# Esp_Companion_V1.net
KiCad netlist of a schematic drawn in EAGLE
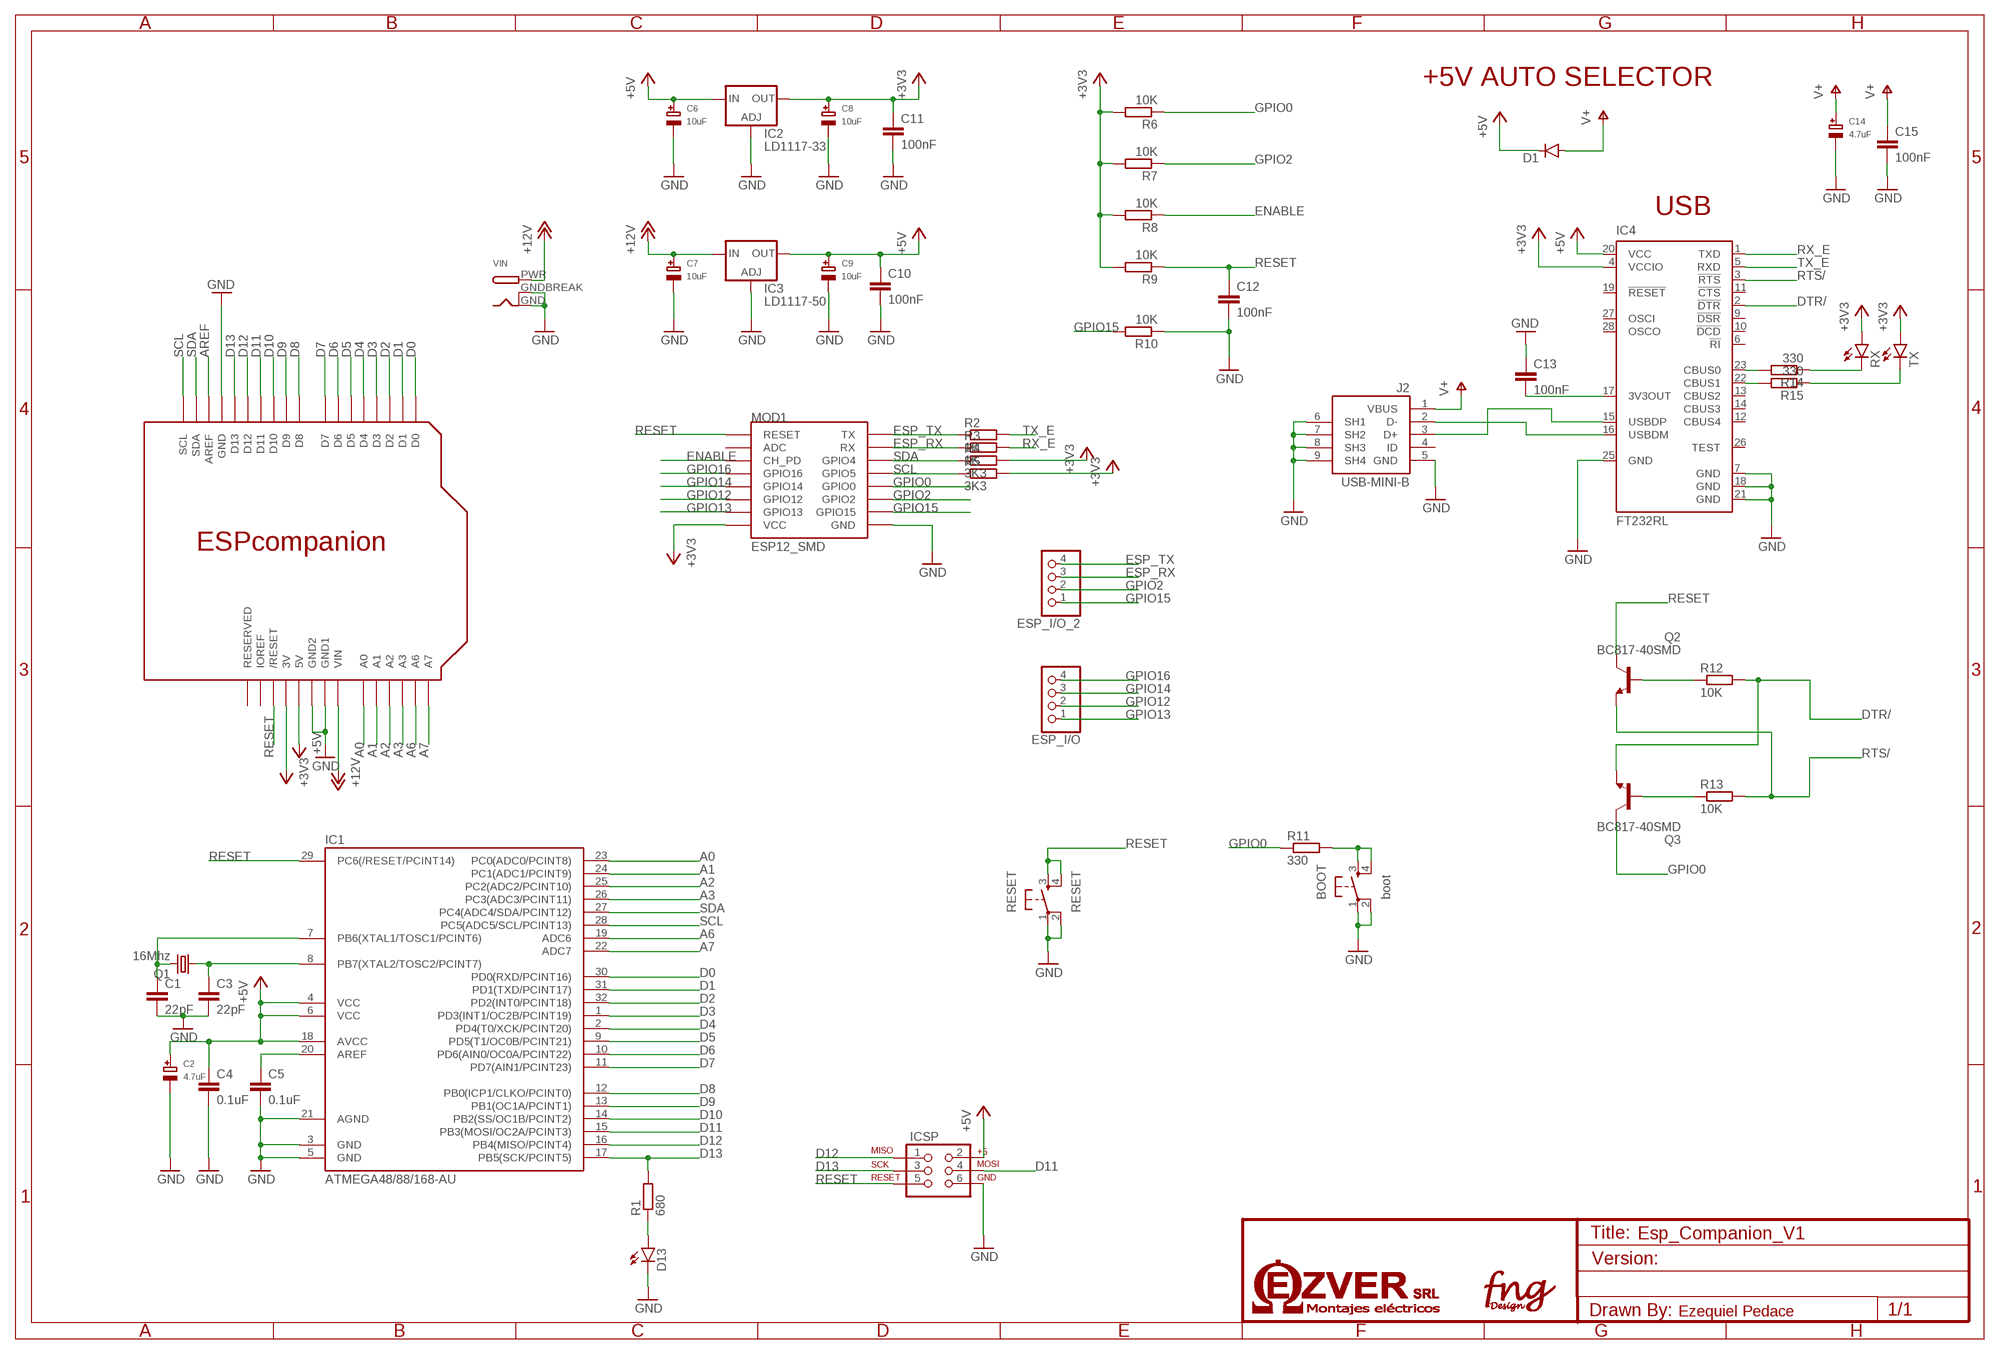
[diagram p0: schematic, sheet 1]

(export (version "E")
  (design (tool "Eeschema 10.0.6"))
  (components
    (comp (ref "BOOT")
      (value "boot")
      (footprint "eagle-import:TACTILE-PTH")
      (libsource (lib "eagle-import") (part "TAC_SWITCHPTH"))
    )
    (comp (ref "C1")
      (value "22pF")
      (footprint "eagle-import:C0603")
      (libsource (lib "eagle-import") (part "C-EUC0603"))
    )
    (comp (ref "C2")
      (value "4.7uF")
      (footprint "eagle-import:EIA3216-18_A-R")
      (libsource (lib "eagle-import") (part "CAP_TANTALUMA/3216_REFLOW"))
    )
    (comp (ref "C3")
      (value "22pF")
      (footprint "eagle-import:C0603")
      (libsource (lib "eagle-import") (part "C-EUC0603"))
    )
    (comp (ref "C4")
      (value "0.1uF")
      (footprint "eagle-import:C0603")
      (libsource (lib "eagle-import") (part "C-EUC0603"))
    )
    (comp (ref "C5")
      (value "0.1uF")
      (footprint "eagle-import:C0603")
      (libsource (lib "eagle-import") (part "C-EUC0603"))
    )
    (comp (ref "C6")
      (value "10uF")
      (footprint "eagle-import:EIA3216-18_A-R")
      (libsource (lib "eagle-import") (part "CAP_TANTALUMA/3216_REFLOW"))
    )
    (comp (ref "C7")
      (value "10uF")
      (footprint "eagle-import:EIA3216-18_A-R")
      (libsource (lib "eagle-import") (part "CAP_TANTALUMA/3216_REFLOW"))
    )
    (comp (ref "C8")
      (value "10uF")
      (footprint "eagle-import:EIA3216-18_A-R")
      (libsource (lib "eagle-import") (part "CAP_TANTALUMA/3216_REFLOW"))
    )
    (comp (ref "C9")
      (value "10uF")
      (footprint "eagle-import:EIA3216-18_A-R")
      (libsource (lib "eagle-import") (part "CAP_TANTALUMA/3216_REFLOW"))
    )
    (comp (ref "C10")
      (value "100nF")
      (footprint "eagle-import:C0603")
      (libsource (lib "eagle-import") (part "C-EUC0603"))
    )
    (comp (ref "C11")
      (value "100nF")
      (footprint "eagle-import:C0603")
      (libsource (lib "eagle-import") (part "C-EUC0603"))
    )
    (comp (ref "C12")
      (value "100nF")
      (footprint "eagle-import:C0603")
      (libsource (lib "eagle-import") (part "C-EUC0603"))
    )
    (comp (ref "C13")
      (value "100nF")
      (footprint "eagle-import:C0603")
      (libsource (lib "eagle-import") (part "C-EUC0603"))
    )
    (comp (ref "C14")
      (value "4.7uF")
      (footprint "eagle-import:EIA3216-18_A-R")
      (libsource (lib "eagle-import") (part "CAP_TANTALUMA/3216_REFLOW"))
    )
    (comp (ref "C15")
      (value "100nF")
      (footprint "eagle-import:C0603")
      (libsource (lib "eagle-import") (part "C-EUC0603"))
    )
    (comp (ref "D1")
      (value "DIODESMA-ALT")
      (footprint "eagle-import:SMA-DIODE_ALT")
      (libsource (lib "eagle-import") (part "DIODESMA-ALT"))
    )
    (comp (ref "D13")
      (value "LED-FKIT-1206")
      (footprint "eagle-import:FKIT-LED-1206")
      (libsource (lib "eagle-import") (part "LED-FKIT-1206"))
    )
    (comp (ref "ESP_I/O")
      (value "PINHD-1X4")
      (footprint "eagle-import:1X04")
      (libsource (lib "eagle-import") (part "PINHD-1X4"))
    )
    (comp (ref "ESP_I/O_2")
      (value "PINHD-1X4")
      (footprint "eagle-import:1X04")
      (libsource (lib "eagle-import") (part "PINHD-1X4"))
    )
    (comp (ref "IC1")
      (value "ATMEGA48/88/168-AU")
      (footprint "eagle-import:TQFP32-08")
      (libsource (lib "eagle-import") (part "ATMEGA48/88/168-AU"))
    )
    (comp (ref "IC2")
      (value "LD1117-33")
      (footprint "eagle-import:DPACK")
      (libsource (lib "eagle-import") (part "LD117A?DT33TR"))
    )
    (comp (ref "IC3")
      (value "LD1117-50")
      (footprint "eagle-import:DPACK")
      (libsource (lib "eagle-import") (part "LD117A?DT33TR"))
    )
    (comp (ref "IC4")
      (value "FT232RL")
      (footprint "eagle-import:SSOP28")
      (libsource (lib "eagle-import") (part "FT232RL"))
    )
    (comp (ref "ICSP")
      (value "AVR_SPI_PRG_62X3_LOCK")
      (footprint "eagle-import:2X3_LOCK")
      (libsource (lib "eagle-import") (part "AVR_SPI_PRG_62X3_LOCK"))
    )
    (comp (ref "J2")
      (value "USB-MINI-B")
      (footprint "eagle-import:USB-MINI-B")
      (libsource (lib "eagle-import") (part "USB-MINI-B"))
    )
    (comp (ref "LAY1")
      (value "ESPCOMPANIONHOLES")
      (footprint "eagle-import:ESPCOMPANION_HOLES")
      (libsource (lib "eagle-import") (part "ESPCOMPANIONHOLES"))
    )
    (comp (ref "MOD1")
      (value "ESP12_SMD")
      (footprint "eagle-import:ESP12_SMD")
      (libsource (lib "eagle-import") (part "ESP12_SMD"))
    )
    (comp (ref "Q1")
      (value "16Mhz")
      (footprint "eagle-import:HC49U70")
      (libsource (lib "eagle-import") (part "CRYSTALHC49U70"))
    )
    (comp (ref "Q2")
      (value "BC817-40SMD")
      (footprint "eagle-import:SOT23-BEC")
      (libsource (lib "eagle-import") (part "BC817SMD-40"))
    )
    (comp (ref "Q3")
      (value "BC817-40SMD")
      (footprint "eagle-import:SOT23-BEC")
      (libsource (lib "eagle-import") (part "BC817SMD-40"))
    )
    (comp (ref "R1")
      (value "680")
      (footprint "eagle-import:R0603")
      (libsource (lib "eagle-import") (part "R-EU_R0603"))
    )
    (comp (ref "R2")
      (value "1K")
      (footprint "eagle-import:R0603")
      (libsource (lib "eagle-import") (part "R-EU_R0603"))
    )
    (comp (ref "R3")
      (value "1K")
      (footprint "eagle-import:R0603")
      (libsource (lib "eagle-import") (part "R-EU_R0603"))
    )
    (comp (ref "R4")
      (value "3K3")
      (footprint "eagle-import:R0603")
      (libsource (lib "eagle-import") (part "R-EU_R0603"))
    )
    (comp (ref "R5")
      (value "3K3")
      (footprint "eagle-import:R0603")
      (libsource (lib "eagle-import") (part "R-EU_R0603"))
    )
    (comp (ref "R6")
      (value "10K")
      (footprint "eagle-import:R0603")
      (libsource (lib "eagle-import") (part "R-EU_R0603"))
    )
    (comp (ref "R7")
      (value "10K")
      (footprint "eagle-import:R0603")
      (libsource (lib "eagle-import") (part "R-EU_R0603"))
    )
    (comp (ref "R8")
      (value "10K")
      (footprint "eagle-import:R0603")
      (libsource (lib "eagle-import") (part "R-EU_R0603"))
    )
    (comp (ref "R9")
      (value "10K")
      (footprint "eagle-import:R0603")
      (libsource (lib "eagle-import") (part "R-EU_R0603"))
    )
    (comp (ref "R10")
      (value "10K")
      (footprint "eagle-import:R0603")
      (libsource (lib "eagle-import") (part "R-EU_R0603"))
    )
    (comp (ref "R11")
      (value "330")
      (footprint "eagle-import:R0603")
      (libsource (lib "eagle-import") (part "R-EU_R0603"))
    )
    (comp (ref "R12")
      (value "10K")
      (footprint "eagle-import:R0603")
      (libsource (lib "eagle-import") (part "R-EU_R0603"))
    )
    (comp (ref "R13")
      (value "10K")
      (footprint "eagle-import:R0603")
      (libsource (lib "eagle-import") (part "R-EU_R0603"))
    )
    (comp (ref "R14")
      (value "330")
      (footprint "eagle-import:R0603")
      (libsource (lib "eagle-import") (part "R-EU_R0603"))
    )
    (comp (ref "R15")
      (value "330")
      (footprint "eagle-import:R0603")
      (libsource (lib "eagle-import") (part "R-EU_R0603"))
    )
    (comp (ref "RESET")
      (value "RESET")
      (footprint "eagle-import:TACTILE-PTH")
      (libsource (lib "eagle-import") (part "TAC_SWITCHPTH"))
    )
    (comp (ref "RX")
      (value "LED-FKIT-1206")
      (footprint "eagle-import:FKIT-LED-1206")
      (libsource (lib "eagle-import") (part "LED-FKIT-1206"))
    )
    (comp (ref "TX")
      (value "LED-FKIT-1206")
      (footprint "eagle-import:FKIT-LED-1206")
      (libsource (lib "eagle-import") (part "LED-FKIT-1206"))
    )
    (comp (ref "VIN")
      (value "DCBARRELPTH")
      (footprint "eagle-import:DCJACK_2MM_PTH")
      (libsource (lib "eagle-import") (part "DCBARRELPTH"))
    )
  )
  (nets
    (net (code "1") (name "+3V3") (class "Default")
      (node (ref "C11") (pin "1") (pinfunction "1_1") (pintype "passive"))
      (node (ref "C8") (pin "+") (pinfunction "+_+") (pintype "passive"))
      (node (ref "IC2") (pin "4") (pinfunction "OUT_4") (pintype "passive"))
      (node (ref "IC4") (pin "4") (pinfunction "VCCIO_4") (pintype "power_in"))
      (node (ref "LAY1") (pin "3V") (pinfunction "3V_3V") (pintype "power_in"))
      (node (ref "MOD1") (pin "P$8") (pinfunction "VCC_P$8") (pintype "bidirectional"))
      (node (ref "R4") (pin "2") (pinfunction "2_2") (pintype "passive"))
      (node (ref "R5") (pin "2") (pinfunction "2_2") (pintype "passive"))
      (node (ref "R6") (pin "2") (pinfunction "2_2") (pintype "passive"))
      (node (ref "R7") (pin "2") (pinfunction "2_2") (pintype "passive"))
      (node (ref "R8") (pin "2") (pinfunction "2_2") (pintype "passive"))
      (node (ref "R9") (pin "2") (pinfunction "2_2") (pintype "passive"))
      (node (ref "RX") (pin "A") (pinfunction "A_A") (pintype "passive"))
      (node (ref "TX") (pin "A") (pinfunction "A_A") (pintype "passive"))
    )
    (net (code "2") (name "+5V") (class "Default")
      (node (ref "C10") (pin "1") (pinfunction "1_1") (pintype "passive"))
      (node (ref "C2") (pin "+") (pinfunction "+_+") (pintype "passive"))
      (node (ref "C4") (pin "1") (pinfunction "1_1") (pintype "passive"))
      (node (ref "C6") (pin "+") (pinfunction "+_+") (pintype "passive"))
      (node (ref "C9") (pin "+") (pinfunction "+_+") (pintype "passive"))
      (node (ref "D1") (pin "C") (pinfunction "C_C") (pintype "passive"))
      (node (ref "IC1") (pin "18") (pinfunction "AVCC_18") (pintype "passive"))
      (node (ref "IC1") (pin "4") (pinfunction "VCC_4") (pintype "power_in"))
      (node (ref "IC1") (pin "6") (pinfunction "VCC_6") (pintype "power_in"))
      (node (ref "IC2") (pin "3") (pinfunction "IN_3") (pintype "input"))
      (node (ref "IC3") (pin "4") (pinfunction "OUT_4") (pintype "passive"))
      (node (ref "IC4") (pin "20") (pinfunction "VCC_20") (pintype "power_in"))
      (node (ref "ICSP") (pin "2") (pinfunction "2_2") (pintype "passive"))
      (node (ref "LAY1") (pin "5V") (pinfunction "5V_5V") (pintype "power_in"))
    )
    (net (code "3") (name "+12V") (class "Default")
      (node (ref "C7") (pin "+") (pinfunction "+_+") (pintype "passive"))
      (node (ref "IC3") (pin "3") (pinfunction "IN_3") (pintype "input"))
      (node (ref "LAY1") (pin "VIN") (pinfunction "VIN_VIN") (pintype "power_in"))
      (node (ref "VIN") (pin "PWR") (pinfunction "PWR_PWR") (pintype "power_in"))
    )
    (net (code "4") (name "/A0") (class "Default")
      (node (ref "IC1") (pin "23") (pinfunction "PC0(ADC0/PCINT8)_23") (pintype "bidirectional"))
      (node (ref "LAY1") (pin "A0") (pinfunction "A0_A0") (pintype "bidirectional"))
    )
    (net (code "5") (name "/A1") (class "Default")
      (node (ref "IC1") (pin "24") (pinfunction "PC1(ADC1/PCINT9)_24") (pintype "bidirectional"))
      (node (ref "LAY1") (pin "A1") (pinfunction "A1_A1") (pintype "bidirectional"))
    )
    (net (code "6") (name "/A2") (class "Default")
      (node (ref "IC1") (pin "25") (pinfunction "PC2(ADC2/PCINT10)_25") (pintype "bidirectional"))
      (node (ref "LAY1") (pin "A2") (pinfunction "A2_A2") (pintype "bidirectional"))
    )
    (net (code "7") (name "/A3") (class "Default")
      (node (ref "IC1") (pin "26") (pinfunction "PC3(ADC3/PCINT11)_26") (pintype "bidirectional"))
      (node (ref "LAY1") (pin "A3") (pinfunction "A3_A3") (pintype "bidirectional"))
    )
    (net (code "8") (name "/A6") (class "Default")
      (node (ref "IC1") (pin "19") (pinfunction "ADC6_19") (pintype "passive"))
      (node (ref "LAY1") (pin "A6") (pinfunction "A6_A6") (pintype "bidirectional"))
    )
    (net (code "9") (name "/A7") (class "Default")
      (node (ref "IC1") (pin "22") (pinfunction "ADC7_22") (pintype "passive"))
      (node (ref "LAY1") (pin "A7") (pinfunction "A7_A7") (pintype "bidirectional"))
    )
    (net (code "10") (name "/AREF") (class "Default")
      (node (ref "LAY1") (pin "AREF") (pinfunction "AREF_AREF") (pintype "bidirectional"))
    )
    (net (code "11") (name "/D0") (class "Default")
      (node (ref "IC1") (pin "30") (pinfunction "PD0(RXD/PCINT16)_30") (pintype "bidirectional"))
      (node (ref "LAY1") (pin "D0") (pinfunction "D0_D0") (pintype "bidirectional"))
    )
    (net (code "12") (name "/D1") (class "Default")
      (node (ref "IC1") (pin "31") (pinfunction "PD1(TXD/PCINT17)_31") (pintype "bidirectional"))
      (node (ref "LAY1") (pin "D1") (pinfunction "D1_D1") (pintype "bidirectional"))
    )
    (net (code "13") (name "/D2") (class "Default")
      (node (ref "IC1") (pin "32") (pinfunction "PD2(INT0/PCINT18)_32") (pintype "bidirectional"))
      (node (ref "LAY1") (pin "D2") (pinfunction "D2_D2") (pintype "bidirectional"))
    )
    (net (code "14") (name "/D3") (class "Default")
      (node (ref "IC1") (pin "1") (pinfunction "PD3(INT1/OC2B/PCINT19)_1") (pintype "bidirectional"))
      (node (ref "LAY1") (pin "D3") (pinfunction "D3_D3") (pintype "bidirectional"))
    )
    (net (code "15") (name "/D4") (class "Default")
      (node (ref "IC1") (pin "2") (pinfunction "PD4(T0/XCK/PCINT20)_2") (pintype "bidirectional"))
      (node (ref "LAY1") (pin "D4") (pinfunction "D4_D4") (pintype "bidirectional"))
    )
    (net (code "16") (name "/D5") (class "Default")
      (node (ref "IC1") (pin "9") (pinfunction "PD5(T1/OC0B/PCINT21)_9") (pintype "bidirectional"))
      (node (ref "LAY1") (pin "D5") (pinfunction "D5_D5") (pintype "bidirectional"))
    )
    (net (code "17") (name "/D6") (class "Default")
      (node (ref "IC1") (pin "10") (pinfunction "PD6(AIN0/OC0A/PCINT22)_10") (pintype "bidirectional"))
      (node (ref "LAY1") (pin "D6") (pinfunction "D6_D6") (pintype "bidirectional"))
    )
    (net (code "18") (name "/D7") (class "Default")
      (node (ref "IC1") (pin "11") (pinfunction "PD7(AIN1/PCINT23)_11") (pintype "bidirectional"))
      (node (ref "LAY1") (pin "D7") (pinfunction "D7_D7") (pintype "bidirectional"))
    )
    (net (code "19") (name "/D8") (class "Default")
      (node (ref "IC1") (pin "12") (pinfunction "PB0(ICP1/CLKO/PCINT0)_12") (pintype "bidirectional"))
      (node (ref "LAY1") (pin "D8") (pinfunction "D8_D8") (pintype "bidirectional"))
    )
    (net (code "20") (name "/D9") (class "Default")
      (node (ref "IC1") (pin "13") (pinfunction "PB1(OC1A/PCINT1)_13") (pintype "bidirectional"))
      (node (ref "LAY1") (pin "D9") (pinfunction "D9_D9") (pintype "bidirectional"))
    )
    (net (code "21") (name "/D10") (class "Default")
      (node (ref "IC1") (pin "14") (pinfunction "PB2(SS/OC1B/PCINT2)_14") (pintype "bidirectional"))
      (node (ref "LAY1") (pin "D10") (pinfunction "D10_D10") (pintype "bidirectional"))
    )
    (net (code "22") (name "/D11") (class "Default")
      (node (ref "IC1") (pin "15") (pinfunction "PB3(MOSI/OC2A/PCINT3)_15") (pintype "bidirectional"))
      (node (ref "ICSP") (pin "4") (pinfunction "4_4") (pintype "passive"))
      (node (ref "LAY1") (pin "D11") (pinfunction "D11_D11") (pintype "bidirectional"))
    )
    (net (code "23") (name "/D12") (class "Default")
      (node (ref "IC1") (pin "16") (pinfunction "PB4(MISO/PCINT4)_16") (pintype "bidirectional"))
      (node (ref "ICSP") (pin "1") (pinfunction "1_1") (pintype "passive"))
      (node (ref "LAY1") (pin "D12") (pinfunction "D12_D12") (pintype "bidirectional"))
    )
    (net (code "24") (name "/D13") (class "Default")
      (node (ref "IC1") (pin "17") (pinfunction "PB5(SCK/PCINT5)_17") (pintype "bidirectional"))
      (node (ref "ICSP") (pin "3") (pinfunction "3_3") (pintype "passive"))
      (node (ref "LAY1") (pin "D13") (pinfunction "D13_D13") (pintype "bidirectional"))
      (node (ref "R1") (pin "2") (pinfunction "2_2") (pintype "passive"))
    )
    (net (code "25") (name "/DTR{slash}") (class "Default")
      (node (ref "IC4") (pin "2") (pinfunction "~{DTR}_2") (pintype "output"))
      (node (ref "Q3") (pin "E") (pinfunction "E_E") (pintype "passive"))
      (node (ref "R12") (pin "2") (pinfunction "2_2") (pintype "passive"))
    )
    (net (code "26") (name "/ENABLE") (class "Default")
      (node (ref "MOD1") (pin "P$3") (pinfunction "CH_PD_P$3") (pintype "bidirectional"))
      (node (ref "R8") (pin "1") (pinfunction "1_1") (pintype "passive"))
    )
    (net (code "27") (name "/ESP_RX") (class "Default")
      (node (ref "ESP_I/O_2") (pin "3") (pinfunction "3_3") (pintype "passive"))
      (node (ref "MOD1") (pin "P$15") (pinfunction "RX_P$15") (pintype "bidirectional"))
      (node (ref "R3") (pin "1") (pinfunction "1_1") (pintype "passive"))
    )
    (net (code "28") (name "/ESP_TX") (class "Default")
      (node (ref "ESP_I/O_2") (pin "4") (pinfunction "4_4") (pintype "passive"))
      (node (ref "MOD1") (pin "P$16") (pinfunction "TX_P$16") (pintype "bidirectional"))
      (node (ref "R2") (pin "1") (pinfunction "1_1") (pintype "passive"))
    )
    (net (code "29") (name "/GPIO0") (class "Default")
      (node (ref "MOD1") (pin "P$12") (pinfunction "GPIO0_P$12") (pintype "bidirectional"))
      (node (ref "Q3") (pin "C") (pinfunction "C_C") (pintype "passive"))
      (node (ref "R11") (pin "1") (pinfunction "1_1") (pintype "passive"))
      (node (ref "R6") (pin "1") (pinfunction "1_1") (pintype "passive"))
    )
    (net (code "30") (name "/GPIO2") (class "Default")
      (node (ref "ESP_I/O_2") (pin "2") (pinfunction "2_2") (pintype "passive"))
      (node (ref "MOD1") (pin "P$11") (pinfunction "GPIO2_P$11") (pintype "bidirectional"))
      (node (ref "R7") (pin "1") (pinfunction "1_1") (pintype "passive"))
    )
    (net (code "31") (name "/GPIO12") (class "Default")
      (node (ref "ESP_I/O") (pin "2") (pinfunction "2_2") (pintype "passive"))
      (node (ref "MOD1") (pin "P$6") (pinfunction "GPIO12_P$6") (pintype "bidirectional"))
    )
    (net (code "32") (name "/GPIO13") (class "Default")
      (node (ref "ESP_I/O") (pin "1") (pinfunction "1_1") (pintype "passive"))
      (node (ref "MOD1") (pin "P$7") (pinfunction "GPIO13_P$7") (pintype "bidirectional"))
    )
    (net (code "33") (name "/GPIO14") (class "Default")
      (node (ref "ESP_I/O") (pin "3") (pinfunction "3_3") (pintype "passive"))
      (node (ref "MOD1") (pin "P$5") (pinfunction "GPIO14_P$5") (pintype "bidirectional"))
    )
    (net (code "34") (name "/GPIO15") (class "Default")
      (node (ref "ESP_I/O_2") (pin "1") (pinfunction "1_1") (pintype "passive"))
      (node (ref "MOD1") (pin "P$10") (pinfunction "GPIO15_P$10") (pintype "bidirectional"))
      (node (ref "R10") (pin "2") (pinfunction "2_2") (pintype "passive"))
    )
    (net (code "35") (name "/GPIO16") (class "Default")
      (node (ref "ESP_I/O") (pin "4") (pinfunction "4_4") (pintype "passive"))
      (node (ref "MOD1") (pin "P$4") (pinfunction "GPIO16_P$4") (pintype "bidirectional"))
    )
    (net (code "36") (name "/RESET") (class "Default")
      (node (ref "C12") (pin "1") (pinfunction "1_1") (pintype "passive"))
      (node (ref "IC1") (pin "29") (pinfunction "PC6(/RESET/PCINT14)_29") (pintype "bidirectional"))
      (node (ref "ICSP") (pin "5") (pinfunction "5_5") (pintype "passive"))
      (node (ref "LAY1") (pin "RESET") (pinfunction "/RESET_RESET") (pintype "bidirectional"))
      (node (ref "MOD1") (pin "P$1") (pinfunction "RESET_P$1") (pintype "bidirectional"))
      (node (ref "Q2") (pin "C") (pinfunction "C_C") (pintype "passive"))
      (node (ref "R9") (pin "1") (pinfunction "1_1") (pintype "passive"))
      (node (ref "RESET") (pin "3") (pinfunction "3_3") (pintype "passive"))
      (node (ref "RESET") (pin "4") (pinfunction "4_4") (pintype "passive"))
    )
    (net (code "37") (name "/RTS{slash}") (class "Default")
      (node (ref "IC4") (pin "3") (pinfunction "~{RTS}_3") (pintype "output"))
      (node (ref "Q2") (pin "E") (pinfunction "E_E") (pintype "passive"))
      (node (ref "R13") (pin "2") (pinfunction "2_2") (pintype "passive"))
    )
    (net (code "38") (name "/RX_E") (class "Default")
      (node (ref "IC4") (pin "1") (pinfunction "TXD_1") (pintype "output"))
      (node (ref "R3") (pin "2") (pinfunction "2_2") (pintype "passive"))
    )
    (net (code "39") (name "/SCL") (class "Default")
      (node (ref "IC1") (pin "28") (pinfunction "PC5(ADC5/SCL/PCINT13)_28") (pintype "bidirectional"))
      (node (ref "LAY1") (pin "SCL") (pinfunction "SCL_SCL") (pintype "bidirectional"))
      (node (ref "MOD1") (pin "P$14") (pinfunction "GPIO5_P$14") (pintype "bidirectional"))
      (node (ref "R5") (pin "1") (pinfunction "1_1") (pintype "passive"))
    )
    (net (code "40") (name "/SDA") (class "Default")
      (node (ref "IC1") (pin "27") (pinfunction "PC4(ADC4/SDA/PCINT12)_27") (pintype "bidirectional"))
      (node (ref "LAY1") (pin "SDA") (pinfunction "SDA_SDA") (pintype "bidirectional"))
      (node (ref "MOD1") (pin "P$13") (pinfunction "GPIO4_P$13") (pintype "bidirectional"))
      (node (ref "R4") (pin "1") (pinfunction "1_1") (pintype "passive"))
    )
    (net (code "41") (name "/TX_E") (class "Default")
      (node (ref "IC4") (pin "5") (pinfunction "RXD_5") (pintype "input"))
      (node (ref "R2") (pin "2") (pinfunction "2_2") (pintype "passive"))
    )
    (net (code "42") (name "GND") (class "Default")
      (node (ref "BOOT") (pin "1") (pinfunction "1_1") (pintype "passive"))
      (node (ref "BOOT") (pin "2") (pinfunction "2_2") (pintype "passive"))
      (node (ref "C1") (pin "2") (pinfunction "2_2") (pintype "passive"))
      (node (ref "C10") (pin "2") (pinfunction "2_2") (pintype "passive"))
      (node (ref "C11") (pin "2") (pinfunction "2_2") (pintype "passive"))
      (node (ref "C12") (pin "2") (pinfunction "2_2") (pintype "passive"))
      (node (ref "C13") (pin "1") (pinfunction "1_1") (pintype "passive"))
      (node (ref "C14") (pin "-") (pinfunction "-_-") (pintype "passive"))
      (node (ref "C15") (pin "2") (pinfunction "2_2") (pintype "passive"))
      (node (ref "C2") (pin "-") (pinfunction "-_-") (pintype "passive"))
      (node (ref "C3") (pin "2") (pinfunction "2_2") (pintype "passive"))
      (node (ref "C4") (pin "2") (pinfunction "2_2") (pintype "passive"))
      (node (ref "C5") (pin "2") (pinfunction "2_2") (pintype "passive"))
      (node (ref "C6") (pin "-") (pinfunction "-_-") (pintype "passive"))
      (node (ref "C7") (pin "-") (pinfunction "-_-") (pintype "passive"))
      (node (ref "C8") (pin "-") (pinfunction "-_-") (pintype "passive"))
      (node (ref "C9") (pin "-") (pinfunction "-_-") (pintype "passive"))
      (node (ref "D13") (pin "C") (pinfunction "C_C") (pintype "passive"))
      (node (ref "IC1") (pin "21") (pinfunction "AGND_21") (pintype "power_in"))
      (node (ref "IC1") (pin "3") (pinfunction "GND_3") (pintype "power_in"))
      (node (ref "IC1") (pin "5") (pinfunction "GND_5") (pintype "power_in"))
      (node (ref "IC2") (pin "1") (pinfunction "ADJ_1") (pintype "input"))
      (node (ref "IC3") (pin "1") (pinfunction "ADJ_1") (pintype "input"))
      (node (ref "IC4") (pin "18") (pinfunction "GND_18") (pintype "power_in"))
      (node (ref "IC4") (pin "21") (pinfunction "GND_21") (pintype "power_in"))
      (node (ref "IC4") (pin "25") (pinfunction "GND_25") (pintype "power_in"))
      (node (ref "IC4") (pin "7") (pinfunction "GND_7") (pintype "power_in"))
      (node (ref "ICSP") (pin "6") (pinfunction "6_6") (pintype "passive"))
      (node (ref "J2") (pin "5") (pinfunction "GND_5") (pintype "power_in"))
      (node (ref "J2") (pin "6") (pinfunction "SH1_6") (pintype "power_in"))
      (node (ref "J2") (pin "7") (pinfunction "SH2_7") (pintype "power_in"))
      (node (ref "J2") (pin "8") (pinfunction "SH3_8") (pintype "power_in"))
      (node (ref "J2") (pin "9") (pinfunction "SH4_9") (pintype "power_in"))
      (node (ref "LAY1") (pin "GND") (pinfunction "GND_GND") (pintype "power_in"))
      (node (ref "LAY1") (pin "GND1") (pinfunction "GND1_GND1") (pintype "power_in"))
      (node (ref "LAY1") (pin "GND2") (pinfunction "GND2_GND2") (pintype "power_in"))
      (node (ref "MOD1") (pin "P$9") (pinfunction "GND_P$9") (pintype "bidirectional"))
      (node (ref "R10") (pin "1") (pinfunction "1_1") (pintype "passive"))
      (node (ref "RESET") (pin "1") (pinfunction "1_1") (pintype "passive"))
      (node (ref "RESET") (pin "2") (pinfunction "2_2") (pintype "passive"))
      (node (ref "VIN") (pin "GND") (pinfunction "GND_GND") (pintype "power_in"))
      (node (ref "VIN") (pin "GNDBREAK") (pinfunction "GNDBREAK_GNDBREAK") (pintype "power_in"))
    )
    (net (code "43") (name "Net-(BOOT-Pad3)") (class "Default")
      (node (ref "BOOT") (pin "3") (pinfunction "3_3") (pintype "passive"))
      (node (ref "BOOT") (pin "4") (pinfunction "4_4") (pintype "passive"))
      (node (ref "R11") (pin "2") (pinfunction "2_2") (pintype "passive"))
    )
    (net (code "44") (name "Net-(D13-PadA)") (class "Default")
      (node (ref "D13") (pin "A") (pinfunction "A_A") (pintype "passive"))
      (node (ref "R1") (pin "1") (pinfunction "1_1") (pintype "passive"))
    )
    (net (code "45") (name "Net-(IC1-AREF)") (class "Default")
      (node (ref "C5") (pin "1") (pinfunction "1_1") (pintype "passive"))
      (node (ref "IC1") (pin "20") (pinfunction "AREF_20") (pintype "passive"))
    )
    (net (code "46") (name "Net-(IC1-PB6(XTAL1{slash}TOSC1{slash}PCINT6))") (class "Default")
      (node (ref "C1") (pin "1") (pinfunction "1_1") (pintype "passive"))
      (node (ref "IC1") (pin "7") (pinfunction "PB6(XTAL1/TOSC1/PCINT6)_7") (pintype "bidirectional"))
      (node (ref "Q1") (pin "2") (pinfunction "2_2") (pintype "passive"))
    )
    (net (code "47") (name "Net-(IC1-PB7(XTAL2{slash}TOSC2{slash}PCINT7))") (class "Default")
      (node (ref "C3") (pin "1") (pinfunction "1_1") (pintype "passive"))
      (node (ref "IC1") (pin "8") (pinfunction "PB7(XTAL2/TOSC2/PCINT7)_8") (pintype "bidirectional"))
      (node (ref "Q1") (pin "1") (pinfunction "1_1") (pintype "passive"))
    )
    (net (code "48") (name "Net-(IC4-3V3OUT)") (class "Default")
      (node (ref "C13") (pin "2") (pinfunction "2_2") (pintype "passive"))
      (node (ref "IC4") (pin "17") (pinfunction "3V3OUT_17") (pintype "output"))
    )
    (net (code "49") (name "Net-(IC4-CBUS0)") (class "Default")
      (node (ref "IC4") (pin "23") (pinfunction "CBUS0_23") (pintype "bidirectional"))
      (node (ref "R14") (pin "2") (pinfunction "2_2") (pintype "passive"))
    )
    (net (code "50") (name "Net-(IC4-CBUS1)") (class "Default")
      (node (ref "IC4") (pin "22") (pinfunction "CBUS1_22") (pintype "bidirectional"))
      (node (ref "R15") (pin "2") (pinfunction "2_2") (pintype "passive"))
    )
    (net (code "51") (name "Net-(IC4-USBDM)") (class "Default")
      (node (ref "IC4") (pin "16") (pinfunction "USBDM_16") (pintype "bidirectional"))
      (node (ref "J2") (pin "2") (pinfunction "D-_2") (pintype "bidirectional"))
    )
    (net (code "52") (name "Net-(IC4-USBDP)") (class "Default")
      (node (ref "IC4") (pin "15") (pinfunction "USBDP_15") (pintype "bidirectional"))
      (node (ref "J2") (pin "3") (pinfunction "D+_3") (pintype "bidirectional"))
    )
    (net (code "53") (name "Net-(Q2-PadB)") (class "Default")
      (node (ref "Q2") (pin "B") (pinfunction "B_B") (pintype "passive"))
      (node (ref "R12") (pin "1") (pinfunction "1_1") (pintype "passive"))
    )
    (net (code "54") (name "Net-(Q3-PadB)") (class "Default")
      (node (ref "Q3") (pin "B") (pinfunction "B_B") (pintype "passive"))
      (node (ref "R13") (pin "1") (pinfunction "1_1") (pintype "passive"))
    )
    (net (code "55") (name "Net-(R14-Pad1)") (class "Default")
      (node (ref "R14") (pin "1") (pinfunction "1_1") (pintype "passive"))
      (node (ref "RX") (pin "C") (pinfunction "C_C") (pintype "passive"))
    )
    (net (code "56") (name "Net-(R15-Pad1)") (class "Default")
      (node (ref "R15") (pin "1") (pinfunction "1_1") (pintype "passive"))
      (node (ref "TX") (pin "C") (pinfunction "C_C") (pintype "passive"))
    )
    (net (code "57") (name "V+") (class "Default")
      (node (ref "C14") (pin "+") (pinfunction "+_+") (pintype "passive"))
      (node (ref "C15") (pin "1") (pinfunction "1_1") (pintype "passive"))
      (node (ref "D1") (pin "A") (pinfunction "A_A") (pintype "passive"))
      (node (ref "J2") (pin "1") (pinfunction "VBUS_1") (pintype "power_in"))
    )
    (net (code "58") (name "unconnected-(IC4-CBUS2-Pad13)") (class "Default")
      (node (ref "IC4") (pin "13") (pinfunction "CBUS2_13") (pintype "bidirectional"))
    )
    (net (code "59") (name "unconnected-(IC4-CBUS3-Pad14)") (class "Default")
      (node (ref "IC4") (pin "14") (pinfunction "CBUS3_14") (pintype "bidirectional"))
    )
    (net (code "60") (name "unconnected-(IC4-CBUS4-Pad12)") (class "Default")
      (node (ref "IC4") (pin "12") (pinfunction "CBUS4_12") (pintype "bidirectional"))
    )
    (net (code "61") (name "unconnected-(IC4-OSCI-Pad27)") (class "Default")
      (node (ref "IC4") (pin "27") (pinfunction "OSCI_27") (pintype "input"))
    )
    (net (code "62") (name "unconnected-(IC4-OSCO-Pad28)") (class "Default")
      (node (ref "IC4") (pin "28") (pinfunction "OSCO_28") (pintype "output"))
    )
    (net (code "63") (name "unconnected-(IC4-TEST-Pad26)") (class "Default")
      (node (ref "IC4") (pin "26") (pinfunction "TEST_26") (pintype "input"))
    )
    (net (code "64") (name "unconnected-(IC4-~{CTS}-Pad11)") (class "Default")
      (node (ref "IC4") (pin "11") (pinfunction "~{CTS}_11") (pintype "input"))
    )
    (net (code "65") (name "unconnected-(IC4-~{DCD}-Pad10)") (class "Default")
      (node (ref "IC4") (pin "10") (pinfunction "~{DCD}_10") (pintype "input"))
    )
    (net (code "66") (name "unconnected-(IC4-~{DSR}-Pad9)") (class "Default")
      (node (ref "IC4") (pin "9") (pinfunction "~{DSR}_9") (pintype "input"))
    )
    (net (code "67") (name "unconnected-(IC4-~{RESET}-Pad19)") (class "Default")
      (node (ref "IC4") (pin "19") (pinfunction "~{RESET}_19") (pintype "input"))
    )
    (net (code "68") (name "unconnected-(IC4-~{RI}-Pad6)") (class "Default")
      (node (ref "IC4") (pin "6") (pinfunction "~{RI}_6") (pintype "input"))
    )
    (net (code "69") (name "unconnected-(J2-ID-Pad4)") (class "Default")
      (node (ref "J2") (pin "4") (pinfunction "ID_4") (pintype "bidirectional"))
    )
    (net (code "70") (name "unconnected-(LAY1-PadIOREF)") (class "Default")
      (node (ref "LAY1") (pin "IOREF") (pinfunction "IOREF_IOREF") (pintype "output"))
    )
    (net (code "71") (name "unconnected-(LAY1-PadRESERVED)") (class "Default")
      (node (ref "LAY1") (pin "RESERVED") (pinfunction "RESERVED_RESERVED") (pintype "no_connect"))
    )
    (net (code "72") (name "unconnected-(MOD1-ADC-PadP$2)") (class "Default")
      (node (ref "MOD1") (pin "P$2") (pinfunction "ADC_P$2") (pintype "bidirectional"))
    )
  )
)
